# 02_ETHERNET.net
KiCad netlist of a schematic drawn in Altium Designer
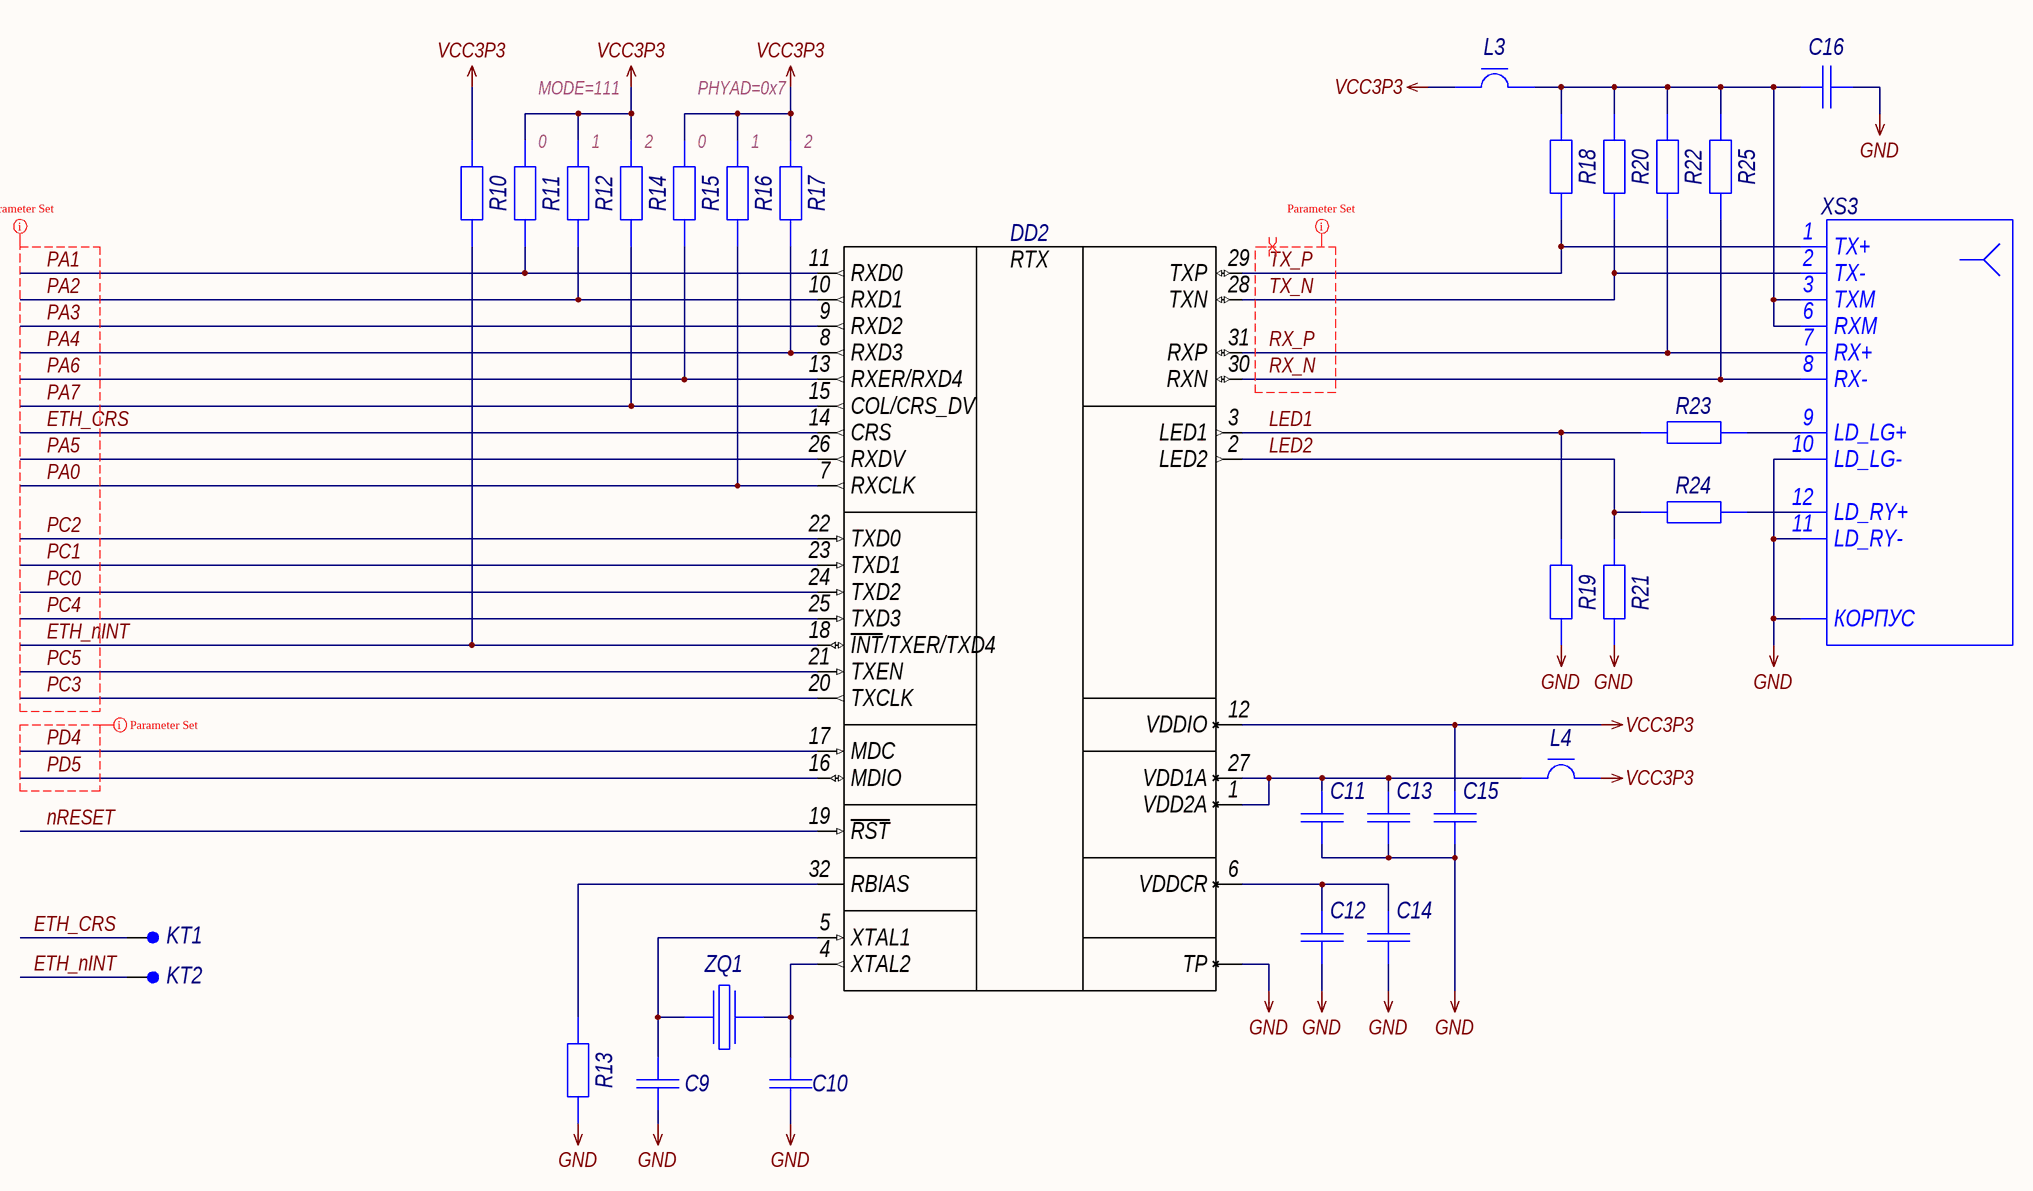
[diagram p0: 02_ETHERNET.SchDoc]

(export (version "E")
  (design (tool "Eeschema 10.0.6"))
  (components
    (comp (ref "C9")
      (value "Capacitor")
      (footprint "C0603_L")
      (fields
        (field (name "PART NUMBER") "GCM1885C2A120JA16D")
        (field (name "VOLTAGE") "100V")
        (field (name "TOLERANCE") "±5%")
        (field (name "PUBLISHER") "Andrew Danich")
      )
      (libsource (lib "ADLib") (part "Capacitor"))
    )
    (comp (ref "C10")
      (value "Capacitor")
      (footprint "C0603_L")
      (fields
        (field (name "PART NUMBER") "GCM1885C2A120JA16D")
        (field (name "VOLTAGE") "100V")
        (field (name "TOLERANCE") "±5%")
        (field (name "PUBLISHER") "Andrew Danich")
      )
      (libsource (lib "ADLib") (part "Capacitor"))
    )
    (comp (ref "C11")
      (value "Capacitor")
      (footprint "C0603_L")
      (fields
        (field (name "PART NUMBER") "GRM188R72A104KA35D")
        (field (name "VOLTAGE") "100V")
        (field (name "TOLERANCE") "±10%")
        (field (name "PUBLISHER") "Andrew Danich")
      )
      (libsource (lib "ADLib") (part "Capacitor"))
    )
    (comp (ref "C12")
      (value "Capacitor")
      (footprint "C0603_L")
      (fields
        (field (name "PART NUMBER") "GCM188R71E105KA64D")
        (field (name "VOLTAGE") "25V")
        (field (name "TOLERANCE") "±10%")
        (field (name "PUBLISHER") "Andrew Danich")
      )
      (libsource (lib "ADLib") (part "Capacitor"))
    )
    (comp (ref "C13")
      (value "Capacitor")
      (footprint "C0603_L")
      (fields
        (field (name "PART NUMBER") "GRM188R72A104KA35D")
        (field (name "VOLTAGE") "100V")
        (field (name "TOLERANCE") "±10%")
        (field (name "PUBLISHER") "Andrew Danich")
      )
      (libsource (lib "ADLib") (part "Capacitor"))
    )
    (comp (ref "C14")
      (value "Capacitor")
      (footprint "C0603_L")
      (fields
        (field (name "PART NUMBER") "GRM1885C1H471FA01D")
        (field (name "VOLTAGE") "50V")
        (field (name "TOLERANCE") "±1%")
        (field (name "PUBLISHER") "Andrew Danich")
      )
      (libsource (lib "ADLib") (part "Capacitor"))
    )
    (comp (ref "C15")
      (value "Capacitor")
      (footprint "C0603_L")
      (fields
        (field (name "PART NUMBER") "GRM188R72A104KA35D")
        (field (name "VOLTAGE") "100V")
        (field (name "TOLERANCE") "±10%")
        (field (name "PUBLISHER") "Andrew Danich")
      )
      (libsource (lib "ADLib") (part "Capacitor"))
    )
    (comp (ref "C16")
      (value "Capacitor")
      (footprint "C0603_L")
      (fields
        (field (name "PART NUMBER") "GRM188R72A104KA35D")
        (field (name "VOLTAGE") "100V")
        (field (name "TOLERANCE") "±10%")
        (field (name "PUBLISHER") "Andrew Danich")
      )
      (libsource (lib "ADLib") (part "Capacitor"))
    )
    (comp (ref "DD2")
      (value "LAN8710A-Series")
      (footprint "QFN-32_050P500X500X085_N")
      (fields
        (field (name "PART NUMBER") "LAN8710A-EZC")
        (field (name "MANUFACTURER") "Microchip")
        (field (name "PUBLISHER") "Andrew Danich")
      )
      (libsource (lib "ADLib") (part "LAN8710A-Series"))
    )
    (comp (ref "KT1")
      (value "Text")
      (footprint "TP-SMT-C-0.8mm")
      (fields (field (name "PART NUMBER") "TestPoint-SMT") (field (name "PUBLISHER") "Andrew Danich"))
      (libsource (lib "ADLib") (part "TP-S-1"))
    )
    (comp (ref "KT2")
      (value "Text")
      (footprint "TP-SMT-C-0.8mm")
      (fields (field (name "PART NUMBER") "TestPoint-SMT") (field (name "PUBLISHER") "Andrew Danich"))
      (libsource (lib "ADLib") (part "TP-S-1"))
    )
    (comp (ref "L3")
      (value "FerriteBead")
      (footprint "L0603_L")
      (fields
        (field (name "PART NUMBER") "BLM18PG331SN1")
        (field (name "MANUFACTURER") "Murata")
        (field (name "PUBLISHER") "Andrew Danich")
      )
      (libsource (lib "ADLib") (part "FerriteBead"))
    )
    (comp (ref "L4")
      (value "FerriteBead")
      (footprint "L0603_L")
      (fields
        (field (name "PART NUMBER") "BLM18PG331SN1")
        (field (name "MANUFACTURER") "Murata")
        (field (name "PUBLISHER") "Andrew Danich")
      )
      (libsource (lib "ADLib") (part "FerriteBead"))
    )
    (comp (ref "R10")
      (value "Resistor")
      (footprint "R0603_L")
      (fields
        (field (name "PART NUMBER") "RC0603JR-0710KL")
        (field (name "TOLERANCE") "±5%")
        (field (name "MANUFACTURER") "Yageo")
        (field (name "PUBLISHER") "Andrew Danich")
      )
      (libsource (lib "ADLib") (part "Resistor"))
    )
    (comp (ref "R11")
      (value "Resistor")
      (footprint "R0603_L")
      (fields
        (field (name "PART NUMBER") "RC0603JR-0710KL")
        (field (name "TOLERANCE") "±5%")
        (field (name "MANUFACTURER") "Yageo")
        (field (name "PUBLISHER") "Andrew Danich")
      )
      (libsource (lib "ADLib") (part "Resistor"))
    )
    (comp (ref "R12")
      (value "Resistor")
      (footprint "R0603_L")
      (fields
        (field (name "PART NUMBER") "RC0603JR-0710KL")
        (field (name "TOLERANCE") "±5%")
        (field (name "MANUFACTURER") "Yageo")
        (field (name "PUBLISHER") "Andrew Danich")
      )
      (libsource (lib "ADLib") (part "Resistor"))
    )
    (comp (ref "R13")
      (value "Resistor")
      (footprint "R0603_L")
      (fields
        (field (name "PART NUMBER") "RC0603FR-0712KL")
        (field (name "TOLERANCE") "±1%")
        (field (name "MANUFACTURER") "Yageo")
        (field (name "PUBLISHER") "Andrew Danich")
      )
      (libsource (lib "ADLib") (part "Resistor"))
    )
    (comp (ref "R14")
      (value "Resistor")
      (footprint "R0603_L")
      (fields
        (field (name "PART NUMBER") "RC0603JR-0710KL")
        (field (name "TOLERANCE") "±5%")
        (field (name "MANUFACTURER") "Yageo")
        (field (name "PUBLISHER") "Andrew Danich")
      )
      (libsource (lib "ADLib") (part "Resistor"))
    )
    (comp (ref "R15")
      (value "Resistor")
      (footprint "R0603_L")
      (fields
        (field (name "PART NUMBER") "RC0603JR-0710KL")
        (field (name "TOLERANCE") "±5%")
        (field (name "MANUFACTURER") "Yageo")
        (field (name "PUBLISHER") "Andrew Danich")
      )
      (libsource (lib "ADLib") (part "Resistor"))
    )
    (comp (ref "R16")
      (value "Resistor")
      (footprint "R0603_L")
      (fields
        (field (name "PART NUMBER") "RC0603JR-0710KL")
        (field (name "TOLERANCE") "±5%")
        (field (name "MANUFACTURER") "Yageo")
        (field (name "PUBLISHER") "Andrew Danich")
      )
      (libsource (lib "ADLib") (part "Resistor"))
    )
    (comp (ref "R17")
      (value "Resistor")
      (footprint "R0603_L")
      (fields
        (field (name "PART NUMBER") "RC0603JR-0710KL")
        (field (name "TOLERANCE") "±5%")
        (field (name "MANUFACTURER") "Yageo")
        (field (name "PUBLISHER") "Andrew Danich")
      )
      (libsource (lib "ADLib") (part "Resistor"))
    )
    (comp (ref "R18")
      (value "Resistor")
      (footprint "R0603_L")
      (fields
        (field (name "PART NUMBER") "RC0603FR-0749R9L")
        (field (name "TOLERANCE") "±1%")
        (field (name "MANUFACTURER") "Yageo")
        (field (name "PUBLISHER") "Andrew Danich")
      )
      (libsource (lib "ADLib") (part "Resistor"))
    )
    (comp (ref "R19")
      (value "Resistor")
      (footprint "R0603_L")
      (fields
        (field (name "PART NUMBER") "RC0603JR-0710KL")
        (field (name "TOLERANCE") "±5%")
        (field (name "MANUFACTURER") "Yageo")
        (field (name "PUBLISHER") "Andrew Danich")
      )
      (libsource (lib "ADLib") (part "Resistor"))
    )
    (comp (ref "R20")
      (value "Resistor")
      (footprint "R0603_L")
      (fields
        (field (name "PART NUMBER") "RC0603FR-0749R9L")
        (field (name "TOLERANCE") "±1%")
        (field (name "MANUFACTURER") "Yageo")
        (field (name "PUBLISHER") "Andrew Danich")
      )
      (libsource (lib "ADLib") (part "Resistor"))
    )
    (comp (ref "R21")
      (value "Resistor")
      (footprint "R0603_L")
      (fields
        (field (name "PART NUMBER") "RC0603JR-0710KL")
        (field (name "TOLERANCE") "±5%")
        (field (name "MANUFACTURER") "Yageo")
        (field (name "PUBLISHER") "Andrew Danich")
      )
      (libsource (lib "ADLib") (part "Resistor"))
    )
    (comp (ref "R22")
      (value "Resistor")
      (footprint "R0603_L")
      (fields
        (field (name "PART NUMBER") "RC0603FR-0749R9L")
        (field (name "TOLERANCE") "±1%")
        (field (name "MANUFACTURER") "Yageo")
        (field (name "PUBLISHER") "Andrew Danich")
      )
      (libsource (lib "ADLib") (part "Resistor"))
    )
    (comp (ref "R23")
      (value "Resistor")
      (footprint "R0603_L")
      (fields
        (field (name "PART NUMBER") "RC0603JR-07270RL")
        (field (name "TOLERANCE") "±5%")
        (field (name "MANUFACTURER") "Yageo")
        (field (name "PUBLISHER") "Andrew Danich")
      )
      (libsource (lib "ADLib") (part "Resistor"))
    )
    (comp (ref "R24")
      (value "Resistor")
      (footprint "R0603_L")
      (fields
        (field (name "PART NUMBER") "RC0603JR-07270RL")
        (field (name "TOLERANCE") "±5%")
        (field (name "MANUFACTURER") "Yageo")
        (field (name "PUBLISHER") "Andrew Danich")
      )
      (libsource (lib "ADLib") (part "Resistor"))
    )
    (comp (ref "R25")
      (value "Resistor")
      (footprint "R0603_L")
      (fields
        (field (name "PART NUMBER") "RC0603FR-0749R9L")
        (field (name "TOLERANCE") "±1%")
        (field (name "MANUFACTURER") "Yageo")
        (field (name "PUBLISHER") "Andrew Danich")
      )
      (libsource (lib "ADLib") (part "Resistor"))
    )
    (comp (ref "XS3")
      (value "Text")
      (footprint "SK02-111006NL")
      (fields
        (field (name "PART NUMBER") "SK02-111006NL")
        (field (name "MANUFACTURER") "Sanken Electric Co., Ltd")
        (field (name "PUBLISHER") "Andrew Danich")
      )
      (libsource (lib "ADLib") (part "SK02-111006NL"))
    )
    (comp (ref "ZQ1")
      (value "Crystal")
      (footprint "SMD 5x3.2mm")
      (fields
        (field (name "PART NUMBER") "AB-25.000MAGE-T")
        (field (name "MANUFACTURER") "TXC Corporation")
        (field (name "PUBLISHER") "Andrew Danich")
      )
      (libsource (lib "ADLib") (part "Crystal"))
    )
  )
  (nets
    (net (code "1") (name "/ETH_CRS") (class "Default")
      (node (ref "DD2") (pin "14") (pinfunction "CRS_14") (pintype "output"))
      (node (ref "KT1") (pin "1") (pinfunction "1_1") (pintype "passive"))
    )
    (net (code "2") (name "/ETH_nINT") (class "Default")
      (node (ref "DD2") (pin "18") (pinfunction "~{INT}/TXER/TXD4_18") (pintype "bidirectional"))
      (node (ref "KT2") (pin "1") (pinfunction "1_1") (pintype "passive"))
      (node (ref "R10") (pin "1") (pinfunction "1_1") (pintype "passive"))
    )
    (net (code "3") (name "/LED1") (class "Default")
      (node (ref "DD2") (pin "3") (pinfunction "LED1_3") (pintype "output"))
      (node (ref "R19") (pin "2") (pinfunction "2_2") (pintype "passive"))
      (node (ref "R23") (pin "1") (pinfunction "1_1") (pintype "passive"))
    )
    (net (code "4") (name "/LED2") (class "Default")
      (node (ref "DD2") (pin "2") (pinfunction "LED2_2") (pintype "output"))
      (node (ref "R21") (pin "2") (pinfunction "2_2") (pintype "passive"))
      (node (ref "R24") (pin "1") (pinfunction "1_1") (pintype "passive"))
    )
    (net (code "5") (name "/PA0") (class "Default")
      (node (ref "DD2") (pin "7") (pinfunction "RXCLK_7") (pintype "output"))
      (node (ref "R16") (pin "1") (pinfunction "1_1") (pintype "passive"))
    )
    (net (code "6") (name "/PA1") (class "Default")
      (node (ref "DD2") (pin "11") (pinfunction "RXD0_11") (pintype "output"))
      (node (ref "R11") (pin "1") (pinfunction "1_1") (pintype "passive"))
    )
    (net (code "7") (name "/PA2") (class "Default")
      (node (ref "DD2") (pin "10") (pinfunction "RXD1_10") (pintype "output"))
      (node (ref "R12") (pin "1") (pinfunction "1_1") (pintype "passive"))
    )
    (net (code "8") (name "/PA3") (class "Default")
      (node (ref "DD2") (pin "9") (pinfunction "RXD2_9") (pintype "output"))
    )
    (net (code "9") (name "/PA4") (class "Default")
      (node (ref "DD2") (pin "8") (pinfunction "RXD3_8") (pintype "output"))
      (node (ref "R17") (pin "1") (pinfunction "1_1") (pintype "passive"))
    )
    (net (code "10") (name "/PA5") (class "Default")
      (node (ref "DD2") (pin "26") (pinfunction "RXDV_26") (pintype "output"))
    )
    (net (code "11") (name "/PA6") (class "Default")
      (node (ref "DD2") (pin "13") (pinfunction "RXER/RXD4_13") (pintype "output"))
      (node (ref "R15") (pin "1") (pinfunction "1_1") (pintype "passive"))
    )
    (net (code "12") (name "/PA7") (class "Default")
      (node (ref "DD2") (pin "15") (pinfunction "COL/CRS_DV_15") (pintype "output"))
      (node (ref "R14") (pin "1") (pinfunction "1_1") (pintype "passive"))
    )
    (net (code "13") (name "/PC0") (class "Default")
      (node (ref "DD2") (pin "24") (pinfunction "TXD2_24") (pintype "input"))
    )
    (net (code "14") (name "/PC1") (class "Default")
      (node (ref "DD2") (pin "23") (pinfunction "TXD1_23") (pintype "input"))
    )
    (net (code "15") (name "/PC2") (class "Default")
      (node (ref "DD2") (pin "22") (pinfunction "TXD0_22") (pintype "input"))
    )
    (net (code "16") (name "/PC3") (class "Default")
      (node (ref "DD2") (pin "20") (pinfunction "TXCLK_20") (pintype "output"))
    )
    (net (code "17") (name "/PC4") (class "Default")
      (node (ref "DD2") (pin "25") (pinfunction "TXD3_25") (pintype "input"))
    )
    (net (code "18") (name "/PC5") (class "Default")
      (node (ref "DD2") (pin "21") (pinfunction "TXEN_21") (pintype "input"))
    )
    (net (code "19") (name "/PD4") (class "Default")
      (node (ref "DD2") (pin "17") (pinfunction "MDC_17") (pintype "input"))
    )
    (net (code "20") (name "/PD5") (class "Default")
      (node (ref "DD2") (pin "16") (pinfunction "MDIO_16") (pintype "bidirectional"))
    )
    (net (code "21") (name "/RX_N") (class "Default")
      (node (ref "DD2") (pin "30") (pinfunction "RXN_30") (pintype "bidirectional"))
      (node (ref "R25") (pin "1") (pinfunction "1_1") (pintype "passive"))
      (node (ref "XS3") (pin "8") (pinfunction "RX-_8") (pintype "passive"))
    )
    (net (code "22") (name "/RX_P") (class "Default")
      (node (ref "DD2") (pin "31") (pinfunction "RXP_31") (pintype "bidirectional"))
      (node (ref "R22") (pin "1") (pinfunction "1_1") (pintype "passive"))
      (node (ref "XS3") (pin "7") (pinfunction "RX+_7") (pintype "passive"))
    )
    (net (code "23") (name "/TX_N") (class "Default")
      (node (ref "DD2") (pin "28") (pinfunction "TXN_28") (pintype "bidirectional"))
      (node (ref "R20") (pin "1") (pinfunction "1_1") (pintype "passive"))
      (node (ref "XS3") (pin "2") (pinfunction "TX-_2") (pintype "passive"))
    )
    (net (code "24") (name "/TX_P") (class "Default")
      (node (ref "DD2") (pin "29") (pinfunction "TXP_29") (pintype "bidirectional"))
      (node (ref "R18") (pin "1") (pinfunction "1_1") (pintype "passive"))
      (node (ref "XS3") (pin "1") (pinfunction "TX+_1") (pintype "passive"))
    )
    (net (code "25") (name "/nRESET") (class "Default")
      (node (ref "DD2") (pin "19") (pinfunction "~{RST}_19") (pintype "input"))
    )
    (net (code "26") (name "GND") (class "Default")
      (node (ref "C10") (pin "1") (pinfunction "1_1") (pintype "passive"))
      (node (ref "C11") (pin "1") (pinfunction "1_1") (pintype "passive"))
      (node (ref "C12") (pin "1") (pinfunction "1_1") (pintype "passive"))
      (node (ref "C13") (pin "1") (pinfunction "1_1") (pintype "passive"))
      (node (ref "C14") (pin "1") (pinfunction "1_1") (pintype "passive"))
      (node (ref "C15") (pin "1") (pinfunction "1_1") (pintype "passive"))
      (node (ref "C16") (pin "2") (pinfunction "2_2") (pintype "passive"))
      (node (ref "C9") (pin "1") (pinfunction "1_1") (pintype "passive"))
      (node (ref "DD2") (pin "TP") (pinfunction "TP_TP") (pintype "power_in"))
      (node (ref "R13") (pin "1") (pinfunction "1_1") (pintype "passive"))
      (node (ref "R19") (pin "1") (pinfunction "1_1") (pintype "passive"))
      (node (ref "R21") (pin "1") (pinfunction "1_1") (pintype "passive"))
      (node (ref "XS3") (pin "10") (pinfunction "LD_LG-_10") (pintype "passive"))
      (node (ref "XS3") (pin "11") (pinfunction "LD_RY-_11") (pintype "passive"))
      (node (ref "XS3") (pin "CASE") (pinfunction "КОРПУС_CASE") (pintype "passive"))
    )
    (net (code "27") (name "Net-(DD2-RBIAS)") (class "Default")
      (node (ref "DD2") (pin "32") (pinfunction "RBIAS_32") (pintype "passive"))
      (node (ref "R13") (pin "2") (pinfunction "2_2") (pintype "passive"))
    )
    (net (code "28") (name "Net-(DD2-VDD1A)") (class "Default")
      (node (ref "C11") (pin "2") (pinfunction "2_2") (pintype "passive"))
      (node (ref "C13") (pin "2") (pinfunction "2_2") (pintype "passive"))
      (node (ref "DD2") (pin "1") (pinfunction "VDD2A_1") (pintype "power_in"))
      (node (ref "DD2") (pin "27") (pinfunction "VDD1A_27") (pintype "power_in"))
      (node (ref "L4") (pin "1") (pinfunction "1_1") (pintype "passive"))
    )
    (net (code "29") (name "Net-(DD2-VDDCR)") (class "Default")
      (node (ref "C12") (pin "2") (pinfunction "2_2") (pintype "passive"))
      (node (ref "C14") (pin "2") (pinfunction "2_2") (pintype "passive"))
      (node (ref "DD2") (pin "6") (pinfunction "VDDCR_6") (pintype "power_in"))
    )
    (net (code "30") (name "Net-(DD2-XTAL1)") (class "Default")
      (node (ref "C9") (pin "2") (pinfunction "2_2") (pintype "passive"))
      (node (ref "DD2") (pin "5") (pinfunction "XTAL1_5") (pintype "input"))
      (node (ref "ZQ1") (pin "1") (pinfunction "1_1") (pintype "passive"))
    )
    (net (code "31") (name "Net-(DD2-XTAL2)") (class "Default")
      (node (ref "C10") (pin "2") (pinfunction "2_2") (pintype "passive"))
      (node (ref "DD2") (pin "4") (pinfunction "XTAL2_4") (pintype "output"))
      (node (ref "ZQ1") (pin "3") (pinfunction "3_3") (pintype "passive"))
    )
    (net (code "32") (name "Net-(XS3-LD_LG+)") (class "Default")
      (node (ref "R23") (pin "2") (pinfunction "2_2") (pintype "passive"))
      (node (ref "XS3") (pin "9") (pinfunction "LD_LG+_9") (pintype "passive"))
    )
    (net (code "33") (name "Net-(XS3-LD_RY+)") (class "Default")
      (node (ref "R24") (pin "2") (pinfunction "2_2") (pintype "passive"))
      (node (ref "XS3") (pin "12") (pinfunction "LD_RY+_12") (pintype "passive"))
    )
    (net (code "34") (name "Net-(XS3-RXM)") (class "Default")
      (node (ref "C16") (pin "1") (pinfunction "1_1") (pintype "passive"))
      (node (ref "L3") (pin "2") (pinfunction "2_2") (pintype "passive"))
      (node (ref "R18") (pin "2") (pinfunction "2_2") (pintype "passive"))
      (node (ref "R20") (pin "2") (pinfunction "2_2") (pintype "passive"))
      (node (ref "R22") (pin "2") (pinfunction "2_2") (pintype "passive"))
      (node (ref "R25") (pin "2") (pinfunction "2_2") (pintype "passive"))
      (node (ref "XS3") (pin "3") (pinfunction "TXM_3") (pintype "passive"))
      (node (ref "XS3") (pin "6") (pinfunction "RXM_6") (pintype "passive"))
    )
    (net (code "35") (name "VCC3P3") (class "Default")
      (node (ref "C15") (pin "2") (pinfunction "2_2") (pintype "passive"))
      (node (ref "DD2") (pin "12") (pinfunction "VDDIO_12") (pintype "power_in"))
      (node (ref "L3") (pin "1") (pinfunction "1_1") (pintype "passive"))
      (node (ref "L4") (pin "2") (pinfunction "2_2") (pintype "passive"))
      (node (ref "R10") (pin "2") (pinfunction "2_2") (pintype "passive"))
      (node (ref "R11") (pin "2") (pinfunction "2_2") (pintype "passive"))
      (node (ref "R12") (pin "2") (pinfunction "2_2") (pintype "passive"))
      (node (ref "R14") (pin "2") (pinfunction "2_2") (pintype "passive"))
      (node (ref "R15") (pin "2") (pinfunction "2_2") (pintype "passive"))
      (node (ref "R16") (pin "2") (pinfunction "2_2") (pintype "passive"))
      (node (ref "R17") (pin "2") (pinfunction "2_2") (pintype "passive"))
    )
  )
)
